# MultiWiiChassis_hexmini_power.net
KiCad netlist of a schematic drawn in EAGLE
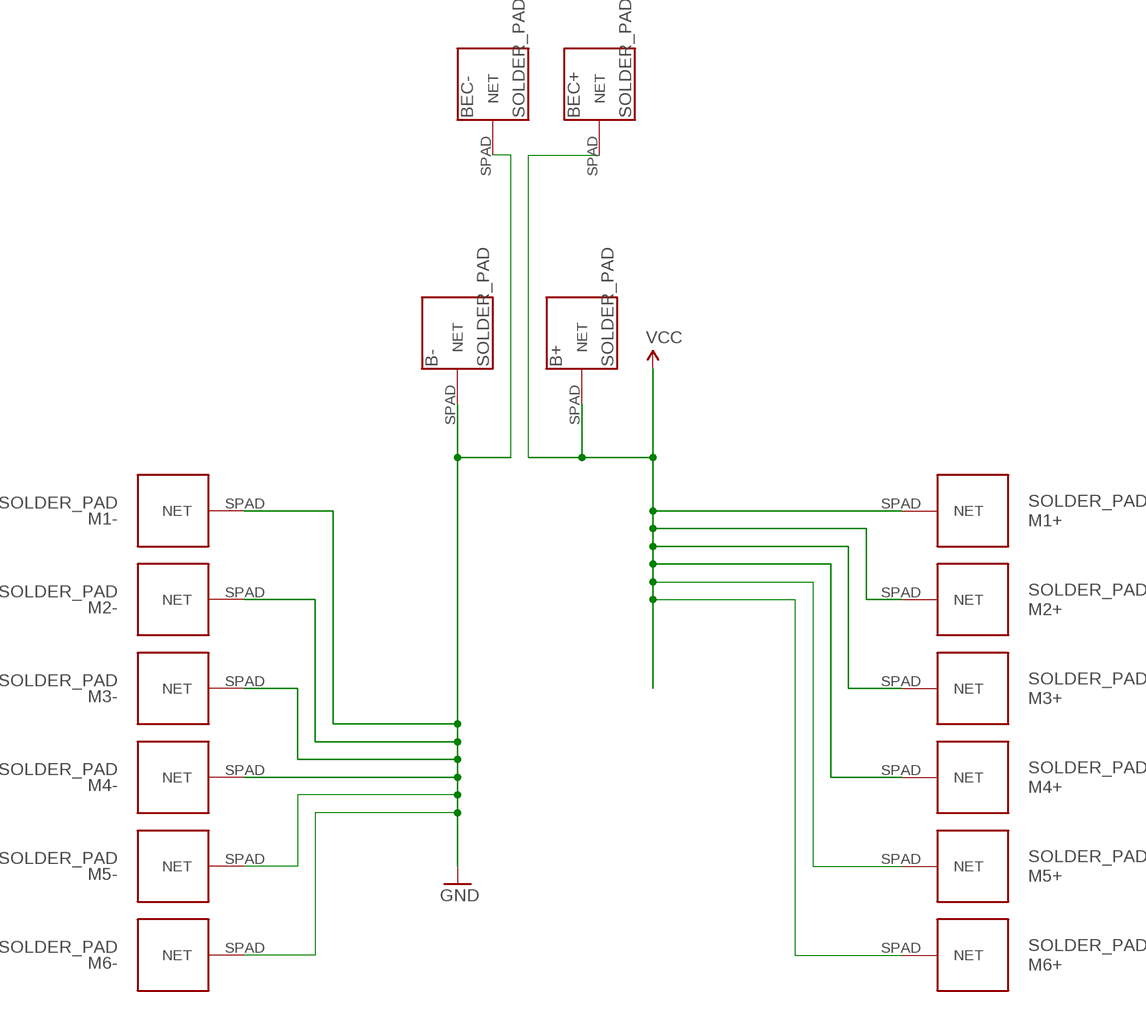
[diagram p0: schematic, sheet 1]

(export (version "E")
  (design (tool "Eeschema 10.0.6"))
  (components
    (comp (ref "B+")
      (value "SOLDER_PAD")
      (footprint "eagle-import:SOLDER_PAD")
      (libsource (lib "eagle-import") (part "SOLDER_PAD"))
    )
    (comp (ref "B-")
      (value "SOLDER_PAD")
      (footprint "eagle-import:SOLDER_PAD")
      (libsource (lib "eagle-import") (part "SOLDER_PAD"))
    )
    (comp (ref "BEC+")
      (value "SOLDER_PAD")
      (footprint "eagle-import:SOLDER_PAD")
      (libsource (lib "eagle-import") (part "SOLDER_PAD"))
    )
    (comp (ref "BEC-")
      (value "SOLDER_PAD")
      (footprint "eagle-import:SOLDER_PAD")
      (libsource (lib "eagle-import") (part "SOLDER_PAD"))
    )
    (comp (ref "M1+")
      (value "SOLDER_PAD")
      (footprint "eagle-import:SOLDER_PAD")
      (libsource (lib "eagle-import") (part "SOLDER_PAD"))
    )
    (comp (ref "M1-")
      (value "SOLDER_PAD")
      (footprint "eagle-import:SOLDER_PAD")
      (libsource (lib "eagle-import") (part "SOLDER_PAD"))
    )
    (comp (ref "M2+")
      (value "SOLDER_PAD")
      (footprint "eagle-import:SOLDER_PAD")
      (libsource (lib "eagle-import") (part "SOLDER_PAD"))
    )
    (comp (ref "M2-")
      (value "SOLDER_PAD")
      (footprint "eagle-import:SOLDER_PAD")
      (libsource (lib "eagle-import") (part "SOLDER_PAD"))
    )
    (comp (ref "M3+")
      (value "SOLDER_PAD")
      (footprint "eagle-import:SOLDER_PAD")
      (libsource (lib "eagle-import") (part "SOLDER_PAD"))
    )
    (comp (ref "M3-")
      (value "SOLDER_PAD")
      (footprint "eagle-import:SOLDER_PAD")
      (libsource (lib "eagle-import") (part "SOLDER_PAD"))
    )
    (comp (ref "M4+")
      (value "SOLDER_PAD")
      (footprint "eagle-import:SOLDER_PAD")
      (libsource (lib "eagle-import") (part "SOLDER_PAD"))
    )
    (comp (ref "M4-")
      (value "SOLDER_PAD")
      (footprint "eagle-import:SOLDER_PAD")
      (libsource (lib "eagle-import") (part "SOLDER_PAD"))
    )
    (comp (ref "M5+")
      (value "SOLDER_PAD")
      (footprint "eagle-import:SOLDER_PAD")
      (libsource (lib "eagle-import") (part "SOLDER_PAD"))
    )
    (comp (ref "M5-")
      (value "SOLDER_PAD")
      (footprint "eagle-import:SOLDER_PAD")
      (libsource (lib "eagle-import") (part "SOLDER_PAD"))
    )
    (comp (ref "M6+")
      (value "SOLDER_PAD")
      (footprint "eagle-import:SOLDER_PAD")
      (libsource (lib "eagle-import") (part "SOLDER_PAD"))
    )
    (comp (ref "M6-")
      (value "SOLDER_PAD")
      (footprint "eagle-import:SOLDER_PAD")
      (libsource (lib "eagle-import") (part "SOLDER_PAD"))
    )
  )
  (nets
    (net (code "1") (name "GND") (class "Default")
      (node (ref "B-") (pin "SPAD") (pinfunction "NET_SPAD") (pintype "bidirectional"))
      (node (ref "BEC-") (pin "SPAD") (pinfunction "NET_SPAD") (pintype "bidirectional"))
      (node (ref "M1-") (pin "SPAD") (pinfunction "NET_SPAD") (pintype "bidirectional"))
      (node (ref "M2-") (pin "SPAD") (pinfunction "NET_SPAD") (pintype "bidirectional"))
      (node (ref "M3-") (pin "SPAD") (pinfunction "NET_SPAD") (pintype "bidirectional"))
      (node (ref "M4-") (pin "SPAD") (pinfunction "NET_SPAD") (pintype "bidirectional"))
      (node (ref "M5-") (pin "SPAD") (pinfunction "NET_SPAD") (pintype "bidirectional"))
      (node (ref "M6-") (pin "SPAD") (pinfunction "NET_SPAD") (pintype "bidirectional"))
    )
    (net (code "2") (name "VCC") (class "Default")
      (node (ref "B+") (pin "SPAD") (pinfunction "NET_SPAD") (pintype "bidirectional"))
      (node (ref "BEC+") (pin "SPAD") (pinfunction "NET_SPAD") (pintype "bidirectional"))
      (node (ref "M1+") (pin "SPAD") (pinfunction "NET_SPAD") (pintype "bidirectional"))
      (node (ref "M2+") (pin "SPAD") (pinfunction "NET_SPAD") (pintype "bidirectional"))
      (node (ref "M3+") (pin "SPAD") (pinfunction "NET_SPAD") (pintype "bidirectional"))
      (node (ref "M4+") (pin "SPAD") (pinfunction "NET_SPAD") (pintype "bidirectional"))
      (node (ref "M5+") (pin "SPAD") (pinfunction "NET_SPAD") (pintype "bidirectional"))
      (node (ref "M6+") (pin "SPAD") (pinfunction "NET_SPAD") (pintype "bidirectional"))
    )
  )
)
